# BMS028B_PinConfig.net
KiCad netlist of a schematic drawn in Altium Designer
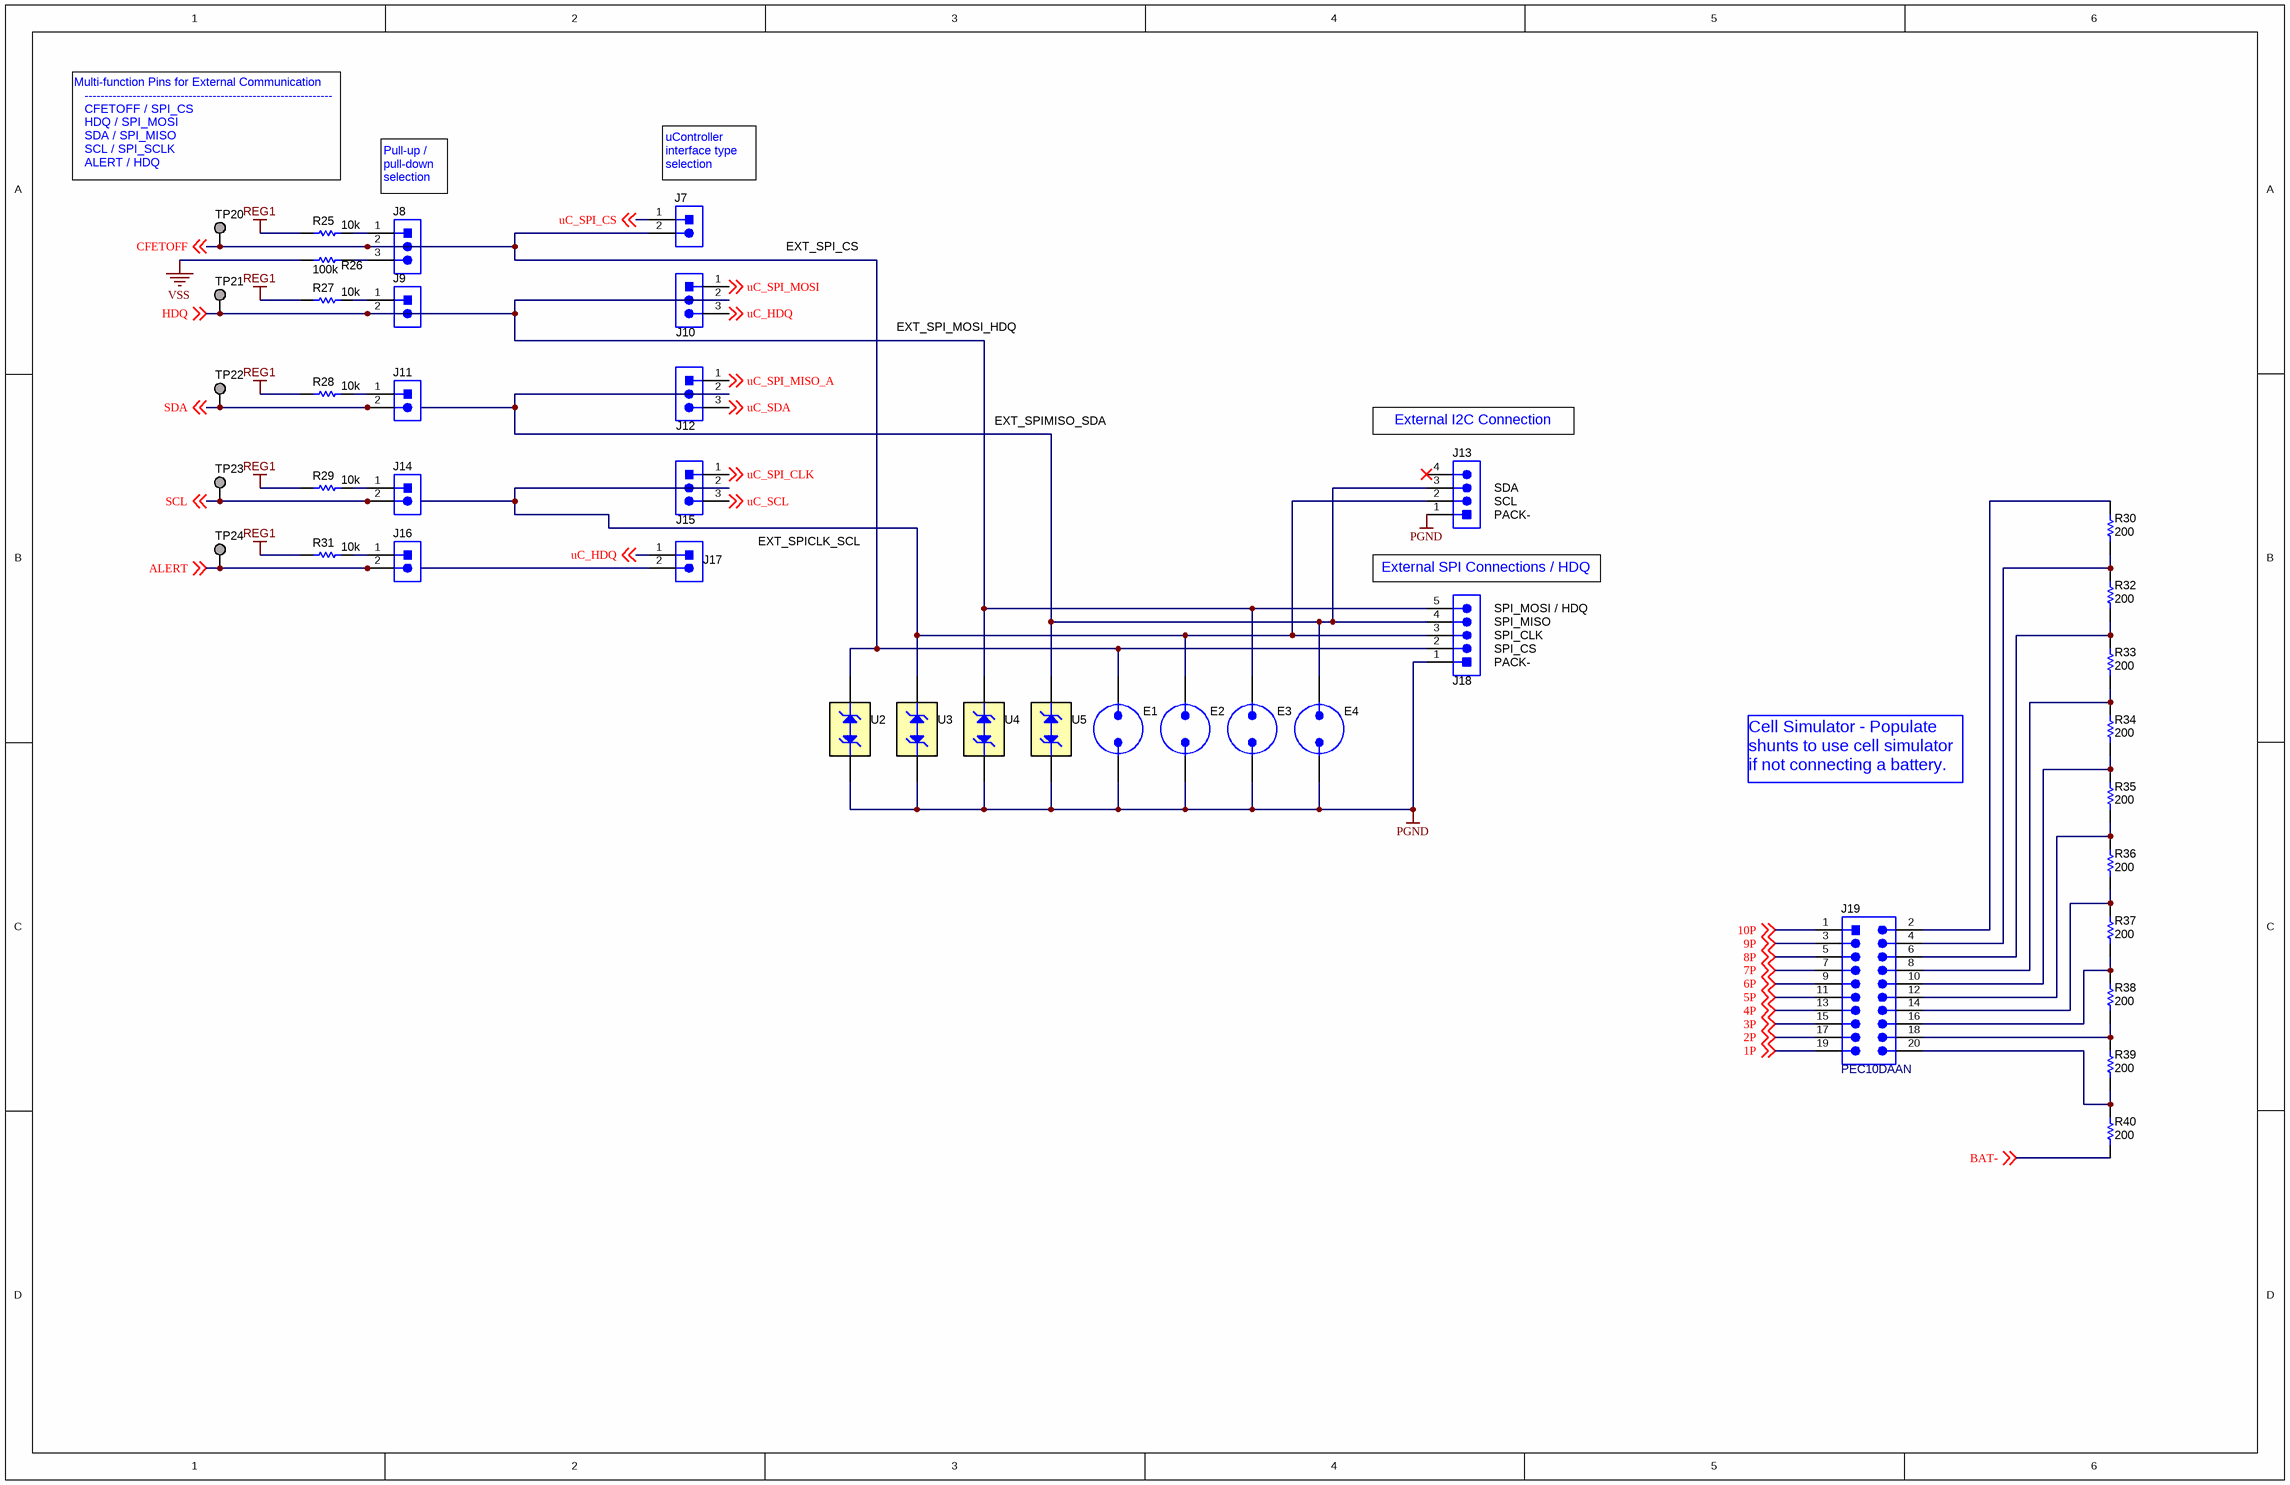
[diagram p0: BMS028B_PinConfig.SchDoc]

(export (version "E")
  (design (tool "Eeschema 10.0.6"))
  (components
    (comp (ref "E1")
      (value "Spark Gap")
      (footprint "SPARK_GAP2")
      (libsource (lib "Altium Vault - TI") (part "CMP-0079939-1"))
    )
    (comp (ref "E2")
      (value "Spark Gap")
      (footprint "SPARK_GAP2")
      (libsource (lib "Altium Vault - TI") (part "CMP-0079939-1"))
    )
    (comp (ref "E3")
      (value "Spark Gap")
      (footprint "SPARK_GAP2")
      (libsource (lib "Altium Vault - TI") (part "CMP-0079939-1"))
    )
    (comp (ref "E4")
      (value "Spark Gap")
      (footprint "SPARK_GAP2")
      (libsource (lib "Altium Vault - TI") (part "CMP-0079939-1"))
    )
    (comp (ref "J7")
      (value "PEC02SAAN")
      (footprint "CONN_PEC02SAAN")
      (description "Header, 100mil, 2x1, Tin, TH")
      (fields
        (field (name "MANUFACTURER") "Sullins Connector Solutions")
        (field (name "PUBLISHER") "Texas Instruments")
      )
      (libsource (lib "Altium Vault - TI") (part "Header_2x1"))
    )
    (comp (ref "J8")
      (value "87898-0304")
      (footprint "Molex_87898-0304")
      (description "Header, 2.54mm, 3x1, Gold, SMT")
      (fields (field (name "MANUFACTURER") "Molex") (field (name "PUBLISHER") "Texas Instruments"))
      (libsource (lib "") (part "CMP-0075388-1_1"))
    )
    (comp (ref "J9")
      (value "PEC02SAAN")
      (footprint "CONN_PEC02SAAN")
      (description "Header, 100mil, 2x1, Tin, TH")
      (fields
        (field (name "MANUFACTURER") "Sullins Connector Solutions")
        (field (name "PUBLISHER") "Texas Instruments")
      )
      (libsource (lib "Altium Vault - TI") (part "Header_2x1"))
    )
    (comp (ref "J10")
      (value "87898-0304")
      (footprint "Molex_87898-0304")
      (description "Header, 2.54mm, 3x1, Gold, SMT")
      (fields (field (name "MANUFACTURER") "Molex") (field (name "PUBLISHER") "Texas Instruments"))
      (libsource (lib "Altium Vault - TI") (part "CMP-0075388-1"))
    )
    (comp (ref "J11")
      (value "PEC02SAAN")
      (footprint "CONN_PEC02SAAN")
      (description "Header, 100mil, 2x1, Tin, TH")
      (fields
        (field (name "MANUFACTURER") "Sullins Connector Solutions")
        (field (name "PUBLISHER") "Texas Instruments")
      )
      (libsource (lib "Altium Vault - TI") (part "Header_2x1"))
    )
    (comp (ref "J12")
      (value "87898-0304")
      (footprint "Molex_87898-0304")
      (description "Header, 2.54mm, 3x1, Gold, SMT")
      (fields (field (name "MANUFACTURER") "Molex") (field (name "PUBLISHER") "Texas Instruments"))
      (libsource (lib "Altium Vault - TI") (part "CMP-0075388-1"))
    )
    (comp (ref "J13")
      (value "22/05/3041")
      (footprint "CONN_22-05-3041")
      (description "Header (friction lock), 100mil, 4x1, R/A, TH")
      (fields (field (name "MANUFACTURER") "Molex") (field (name "PUBLISHER") "Texas Instruments"))
      (libsource (lib "Altium Vault - TI") (part "CMP-0055187-1"))
    )
    (comp (ref "J14")
      (value "PEC02SAAN")
      (footprint "CONN_PEC02SAAN")
      (description "Header, 100mil, 2x1, Tin, TH")
      (fields
        (field (name "MANUFACTURER") "Sullins Connector Solutions")
        (field (name "PUBLISHER") "Texas Instruments")
      )
      (libsource (lib "Altium Vault - TI") (part "Header_2x1"))
    )
    (comp (ref "J15")
      (value "87898-0304")
      (footprint "Molex_87898-0304")
      (description "Header, 2.54mm, 3x1, Gold, SMT")
      (fields (field (name "MANUFACTURER") "Molex") (field (name "PUBLISHER") "Texas Instruments"))
      (libsource (lib "Altium Vault - TI") (part "CMP-0075388-1"))
    )
    (comp (ref "J16")
      (value "PEC02SAAN")
      (footprint "CONN_PEC02SAAN")
      (description "Header, 100mil, 2x1, Tin, TH")
      (fields
        (field (name "MANUFACTURER") "Sullins Connector Solutions")
        (field (name "PUBLISHER") "Texas Instruments")
      )
      (libsource (lib "Altium Vault - TI") (part "Header_2x1"))
    )
    (comp (ref "J17")
      (value "PEC02SAAN")
      (footprint "CONN_PEC02SAAN")
      (description "Header, 100mil, 2x1, Tin, TH")
      (fields
        (field (name "MANUFACTURER") "Sullins Connector Solutions")
        (field (name "PUBLISHER") "Texas Instruments")
      )
      (libsource (lib "Altium Vault - TI") (part "Header_2x1"))
    )
    (comp (ref "J18")
      (value "PEC05SAAN")
      (footprint "Sullins_PxC05SAAN")
      (description "Header, 2.54mm, 5x1, Tin, TH")
      (fields
        (field (name "MANUFACTURER") "Sullins Connector Solutions")
        (field (name "PUBLISHER") "Texas Instruments")
      )
      (libsource (lib "Altium Vault - TI") (part "CMP-0054597-1"))
    )
    (comp (ref "J19")
      (value "PEC10DAAN")
      (footprint "SULLINS_PEC10DAAN")
      (description "Header, 2.54mm, 10x2, Tin, TH")
      (fields (field (name "MANUFACTURER") "Sullins Connector Solutions"))
      (libsource (lib "Altium Vault - TI") (part "Header_10x2"))
    )
    (comp (ref "R25")
      (value "CRCW060310K0JNEA")
      (footprint "0603")
      (description "RES, 10 k, 5%, 0.1 W, AEC-Q200 Grade 0, 0603")
      (fields (field (name "MANUFACTURER") "Vishay-Dale") (field (name "VALUEDISPLAYED") "10k"))
      (libsource (lib "Altium Vault - TI") (part "CMP-0025701-4"))
    )
    (comp (ref "R26")
      (value "CRCW0603100KJNEA")
      (footprint "0603")
      (description "RES, 100 k, 5%, 0.1 W, AEC-Q200 Grade 0, 0603")
      (fields (field (name "MANUFACTURER") "Vishay-Dale") (field (name "VALUEDISPLAYED") "100k"))
      (libsource (lib "Altium Vault - TI") (part "Resistor"))
    )
    (comp (ref "R27")
      (value "CRCW060310K0JNEA")
      (footprint "0603")
      (description "RES, 10 k, 5%, 0.1 W, AEC-Q200 Grade 0, 0603")
      (fields (field (name "MANUFACTURER") "Vishay-Dale") (field (name "VALUEDISPLAYED") "10k"))
      (libsource (lib "Altium Vault - TI") (part "CMP-0025701-4"))
    )
    (comp (ref "R28")
      (value "CRCW060310K0JNEA")
      (footprint "0603")
      (description "RES, 10 k, 5%, 0.1 W, AEC-Q200 Grade 0, 0603")
      (fields (field (name "MANUFACTURER") "Vishay-Dale") (field (name "VALUEDISPLAYED") "10k"))
      (libsource (lib "Altium Vault - TI") (part "CMP-0025701-4"))
    )
    (comp (ref "R29")
      (value "CRCW060310K0JNEA")
      (footprint "0603")
      (description "RES, 10 k, 5%, 0.1 W, AEC-Q200 Grade 0, 0603")
      (fields (field (name "MANUFACTURER") "Vishay-Dale") (field (name "VALUEDISPLAYED") "10k"))
      (libsource (lib "Altium Vault - TI") (part "CMP-0025701-4"))
    )
    (comp (ref "R30")
      (value "CRCW1206200RFKEA")
      (footprint "1206")
      (description "RES, 200, 1%, 0.25 W, AEC-Q200 Grade 0, 1206")
      (fields (field (name "MANUFACTURER") "Vishay-Dale") (field (name "VALUEDISPLAYED") "200"))
      (libsource (lib "Altium Vault - TI") (part "Resistor"))
    )
    (comp (ref "R31")
      (value "CRCW060310K0JNEA")
      (footprint "0603")
      (description "RES, 10 k, 5%, 0.1 W, AEC-Q200 Grade 0, 0603")
      (fields (field (name "MANUFACTURER") "Vishay-Dale") (field (name "VALUEDISPLAYED") "10k"))
      (libsource (lib "Altium Vault - TI") (part "CMP-0025701-4"))
    )
    (comp (ref "R32")
      (value "CRCW1206200RFKEA")
      (footprint "1206")
      (description "RES, 200, 1%, 0.25 W, AEC-Q200 Grade 0, 1206")
      (fields (field (name "MANUFACTURER") "Vishay-Dale") (field (name "VALUEDISPLAYED") "200"))
      (libsource (lib "Altium Vault - TI") (part "Resistor"))
    )
    (comp (ref "R33")
      (value "CRCW1206200RFKEA")
      (footprint "1206")
      (description "RES, 200, 1%, 0.25 W, AEC-Q200 Grade 0, 1206")
      (fields (field (name "MANUFACTURER") "Vishay-Dale") (field (name "VALUEDISPLAYED") "200"))
      (libsource (lib "Altium Vault - TI") (part "Resistor"))
    )
    (comp (ref "R34")
      (value "CRCW1206200RFKEA")
      (footprint "1206")
      (description "RES, 200, 1%, 0.25 W, AEC-Q200 Grade 0, 1206")
      (fields (field (name "MANUFACTURER") "Vishay-Dale") (field (name "VALUEDISPLAYED") "200"))
      (libsource (lib "Altium Vault - TI") (part "Resistor"))
    )
    (comp (ref "R35")
      (value "CRCW1206200RFKEA")
      (footprint "1206")
      (description "RES, 200, 1%, 0.25 W, AEC-Q200 Grade 0, 1206")
      (fields (field (name "MANUFACTURER") "Vishay-Dale") (field (name "VALUEDISPLAYED") "200"))
      (libsource (lib "Altium Vault - TI") (part "Resistor"))
    )
    (comp (ref "R36")
      (value "CRCW1206200RFKEA")
      (footprint "1206")
      (description "RES, 200, 1%, 0.25 W, AEC-Q200 Grade 0, 1206")
      (fields (field (name "MANUFACTURER") "Vishay-Dale") (field (name "VALUEDISPLAYED") "200"))
      (libsource (lib "Altium Vault - TI") (part "Resistor"))
    )
    (comp (ref "R37")
      (value "CRCW1206200RFKEA")
      (footprint "1206")
      (description "RES, 200, 1%, 0.25 W, AEC-Q200 Grade 0, 1206")
      (fields (field (name "MANUFACTURER") "Vishay-Dale") (field (name "VALUEDISPLAYED") "200"))
      (libsource (lib "Altium Vault - TI") (part "Resistor"))
    )
    (comp (ref "R38")
      (value "CRCW1206200RFKEA")
      (footprint "1206")
      (description "RES, 200, 1%, 0.25 W, AEC-Q200 Grade 0, 1206")
      (fields (field (name "MANUFACTURER") "Vishay-Dale") (field (name "VALUEDISPLAYED") "200"))
      (libsource (lib "Altium Vault - TI") (part "Resistor"))
    )
    (comp (ref "R39")
      (value "CRCW1206200RFKEA")
      (footprint "1206")
      (description "RES, 200, 1%, 0.25 W, AEC-Q200 Grade 0, 1206")
      (fields (field (name "MANUFACTURER") "Vishay-Dale") (field (name "VALUEDISPLAYED") "200"))
      (libsource (lib "Altium Vault - TI") (part "Resistor"))
    )
    (comp (ref "R40")
      (value "CRCW1206200RFKEA")
      (footprint "1206")
      (description "RES, 200, 1%, 0.25 W, AEC-Q200 Grade 0, 1206")
      (fields (field (name "MANUFACTURER") "Vishay-Dale") (field (name "VALUEDISPLAYED") "200"))
      (libsource (lib "Altium Vault - TI") (part "Resistor"))
    )
    (comp (ref "TP20")
      (value "TESTPOINT")
      (footprint "TP_50MIL-25MILHOLE")
      (description "TEST POINT.  No entry in BOM.")
      (libsource (lib "Altium Vault - TI") (part "TESTPOINT"))
    )
    (comp (ref "TP21")
      (value "TESTPOINT")
      (footprint "TP_50MIL-25MILHOLE")
      (description "TEST POINT.  No entry in BOM.")
      (libsource (lib "Altium Vault - TI") (part "TESTPOINT"))
    )
    (comp (ref "TP22")
      (value "TESTPOINT")
      (footprint "TP_50MIL-25MILHOLE")
      (description "TEST POINT.  No entry in BOM.")
      (libsource (lib "Altium Vault - TI") (part "TESTPOINT"))
    )
    (comp (ref "TP23")
      (value "TESTPOINT")
      (footprint "TP_50MIL-25MILHOLE")
      (description "TEST POINT.  No entry in BOM.")
      (libsource (lib "Altium Vault - TI") (part "TESTPOINT"))
    )
    (comp (ref "TP24")
      (value "TESTPOINT")
      (footprint "TP_50MIL-25MILHOLE")
      (description "TEST POINT.  No entry in BOM.")
      (libsource (lib "Altium Vault - TI") (part "TESTPOINT"))
    )
    (comp (ref "U2")
      (value "TPD1E10B06DPYR")
      (footprint "DPY0002A")
      (description "Single-Channel ESD in 0402 Package With 10pF Capacitance and 6V Breakdown, DPY0002A (X1SON-2)")
      (fields
        (field (name "MANUFACTURER") "Texas Instruments")
        (field (name "ALTERNATE PARTNUMBER") "TPD1E10B06DPYT")
      )
      (libsource (lib "Altium Vault - TI") (part "TPD1E10B06"))
    )
    (comp (ref "U3")
      (value "TPD1E10B06DPYR")
      (footprint "DPY0002A")
      (description "Single-Channel ESD in 0402 Package With 10pF Capacitance and 6V Breakdown, DPY0002A (X1SON-2)")
      (fields
        (field (name "MANUFACTURER") "Texas Instruments")
        (field (name "ALTERNATE PARTNUMBER") "TPD1E10B06DPYT")
      )
      (libsource (lib "Altium Vault - TI") (part "TPD1E10B06"))
    )
    (comp (ref "U4")
      (value "TPD1E10B06DPYR")
      (footprint "DPY0002A")
      (description "Single-Channel ESD in 0402 Package With 10pF Capacitance and 6V Breakdown, DPY0002A (X1SON-2)")
      (fields
        (field (name "MANUFACTURER") "Texas Instruments")
        (field (name "ALTERNATE PARTNUMBER") "TPD1E10B06DPYT")
      )
      (libsource (lib "Altium Vault - TI") (part "TPD1E10B06"))
    )
    (comp (ref "U5")
      (value "TPD1E10B06DPYR")
      (footprint "DPY0002A")
      (description "Single-Channel ESD in 0402 Package With 10pF Capacitance and 6V Breakdown, DPY0002A (X1SON-2)")
      (fields
        (field (name "MANUFACTURER") "Texas Instruments")
        (field (name "ALTERNATE PARTNUMBER") "TPD1E10B06DPYT")
      )
      (libsource (lib "Altium Vault - TI") (part "TPD1E10B06"))
    )
  )
  (nets
    (net (code "1") (name "1P") (class "Default")
      (node (ref "J19") (pin "19") (pinfunction "19_19") (pintype "passive"))
    )
    (net (code "2") (name "2P") (class "Default")
      (node (ref "J19") (pin "17") (pinfunction "17_17") (pintype "passive"))
    )
    (net (code "3") (name "3P") (class "Default")
      (node (ref "J19") (pin "15") (pinfunction "15_15") (pintype "passive"))
    )
    (net (code "4") (name "4P") (class "Default")
      (node (ref "J19") (pin "13") (pinfunction "13_13") (pintype "passive"))
    )
    (net (code "5") (name "5P") (class "Default")
      (node (ref "J19") (pin "11") (pinfunction "11_11") (pintype "passive"))
    )
    (net (code "6") (name "6P") (class "Default")
      (node (ref "J19") (pin "9") (pinfunction "9_9") (pintype "passive"))
    )
    (net (code "7") (name "7P") (class "Default")
      (node (ref "J19") (pin "7") (pinfunction "7_7") (pintype "passive"))
    )
    (net (code "8") (name "8P") (class "Default")
      (node (ref "J19") (pin "5") (pinfunction "5_5") (pintype "passive"))
    )
    (net (code "9") (name "9P") (class "Default")
      (node (ref "J19") (pin "3") (pinfunction "3_3") (pintype "passive"))
    )
    (net (code "10") (name "10P") (class "Default")
      (node (ref "J19") (pin "1") (pinfunction "1_1") (pintype "passive"))
    )
    (net (code "11") (name "ALERT") (class "Default")
      (node (ref "J16") (pin "2") (pinfunction "2_2") (pintype "passive"))
      (node (ref "J17") (pin "2") (pinfunction "2_2") (pintype "passive"))
      (node (ref "TP24") (pin "1") (pintype "passive"))
    )
    (net (code "12") (name "BAT-") (class "Default")
      (node (ref "R40") (pin "1") (pinfunction "1_1") (pintype "passive"))
    )
    (net (code "13") (name "CFETOFF") (class "Default")
      (node (ref "E1") (pin "1") (pinfunction "1_1") (pintype "passive"))
      (node (ref "J18") (pin "2") (pinfunction "2_2") (pintype "passive"))
      (node (ref "J7") (pin "2") (pinfunction "2_2") (pintype "passive"))
      (node (ref "J8") (pin "2") (pinfunction "2_2") (pintype "passive"))
      (node (ref "TP20") (pin "1") (pintype "passive"))
      (node (ref "U2") (pin "1") (pinfunction "K_1") (pintype "passive"))
    )
    (net (code "14") (name "HDQ") (class "Default")
      (node (ref "E3") (pin "1") (pinfunction "1_1") (pintype "passive"))
      (node (ref "J10") (pin "2") (pinfunction "2_2") (pintype "passive"))
      (node (ref "J18") (pin "5") (pinfunction "5_5") (pintype "passive"))
      (node (ref "J9") (pin "2") (pinfunction "2_2") (pintype "passive"))
      (node (ref "TP21") (pin "1") (pintype "passive"))
      (node (ref "U4") (pin "1") (pinfunction "K_1") (pintype "passive"))
    )
    (net (code "15") (name "Net-(J8-Pad1)") (class "Default")
      (node (ref "J8") (pin "1") (pinfunction "1_1") (pintype "passive"))
      (node (ref "R25") (pin "2") (pinfunction "2_2") (pintype "passive"))
    )
    (net (code "16") (name "Net-(J8-Pad3)") (class "Default")
      (node (ref "J8") (pin "3") (pinfunction "3_3") (pintype "passive"))
      (node (ref "R26") (pin "2") (pinfunction "2_2") (pintype "passive"))
    )
    (net (code "17") (name "Net-(J9-Pad1)") (class "Default")
      (node (ref "J9") (pin "1") (pinfunction "1_1") (pintype "passive"))
      (node (ref "R27") (pin "2") (pinfunction "2_2") (pintype "passive"))
    )
    (net (code "18") (name "Net-(J11-Pad1)") (class "Default")
      (node (ref "J11") (pin "1") (pinfunction "1_1") (pintype "passive"))
      (node (ref "R28") (pin "2") (pinfunction "2_2") (pintype "passive"))
    )
    (net (code "19") (name "Net-(J14-Pad1)") (class "Default")
      (node (ref "J14") (pin "1") (pinfunction "1_1") (pintype "passive"))
      (node (ref "R29") (pin "2") (pinfunction "2_2") (pintype "passive"))
    )
    (net (code "20") (name "Net-(J16-Pad1)") (class "Default")
      (node (ref "J16") (pin "1") (pinfunction "1_1") (pintype "passive"))
      (node (ref "R31") (pin "2") (pinfunction "2_2") (pintype "passive"))
    )
    (net (code "21") (name "Net-(J19-Pad2)") (class "Default")
      (node (ref "J19") (pin "2") (pinfunction "2_2") (pintype "passive"))
      (node (ref "R30") (pin "2") (pinfunction "2_2") (pintype "passive"))
    )
    (net (code "22") (name "Net-(J19-Pad4)") (class "Default")
      (node (ref "J19") (pin "4") (pinfunction "4_4") (pintype "passive"))
      (node (ref "R30") (pin "1") (pinfunction "1_1") (pintype "passive"))
      (node (ref "R32") (pin "2") (pinfunction "2_2") (pintype "passive"))
    )
    (net (code "23") (name "Net-(J19-Pad6)") (class "Default")
      (node (ref "J19") (pin "6") (pinfunction "6_6") (pintype "passive"))
      (node (ref "R32") (pin "1") (pinfunction "1_1") (pintype "passive"))
      (node (ref "R33") (pin "2") (pinfunction "2_2") (pintype "passive"))
    )
    (net (code "24") (name "Net-(J19-Pad8)") (class "Default")
      (node (ref "J19") (pin "8") (pinfunction "8_8") (pintype "passive"))
      (node (ref "R33") (pin "1") (pinfunction "1_1") (pintype "passive"))
      (node (ref "R34") (pin "2") (pinfunction "2_2") (pintype "passive"))
    )
    (net (code "25") (name "Net-(J19-Pad10)") (class "Default")
      (node (ref "J19") (pin "10") (pinfunction "10_10") (pintype "passive"))
      (node (ref "R34") (pin "1") (pinfunction "1_1") (pintype "passive"))
      (node (ref "R35") (pin "2") (pinfunction "2_2") (pintype "passive"))
    )
    (net (code "26") (name "Net-(J19-Pad12)") (class "Default")
      (node (ref "J19") (pin "12") (pinfunction "12_12") (pintype "passive"))
      (node (ref "R35") (pin "1") (pinfunction "1_1") (pintype "passive"))
      (node (ref "R36") (pin "2") (pinfunction "2_2") (pintype "passive"))
    )
    (net (code "27") (name "Net-(J19-Pad14)") (class "Default")
      (node (ref "J19") (pin "14") (pinfunction "14_14") (pintype "passive"))
      (node (ref "R36") (pin "1") (pinfunction "1_1") (pintype "passive"))
      (node (ref "R37") (pin "2") (pinfunction "2_2") (pintype "passive"))
    )
    (net (code "28") (name "Net-(J19-Pad16)") (class "Default")
      (node (ref "J19") (pin "16") (pinfunction "16_16") (pintype "passive"))
      (node (ref "R37") (pin "1") (pinfunction "1_1") (pintype "passive"))
      (node (ref "R38") (pin "2") (pinfunction "2_2") (pintype "passive"))
    )
    (net (code "29") (name "Net-(J19-Pad18)") (class "Default")
      (node (ref "J19") (pin "18") (pinfunction "18_18") (pintype "passive"))
      (node (ref "R38") (pin "1") (pinfunction "1_1") (pintype "passive"))
      (node (ref "R39") (pin "2") (pinfunction "2_2") (pintype "passive"))
    )
    (net (code "30") (name "Net-(J19-Pad20)") (class "Default")
      (node (ref "J19") (pin "20") (pinfunction "20_20") (pintype "passive"))
      (node (ref "R39") (pin "1") (pinfunction "1_1") (pintype "passive"))
      (node (ref "R40") (pin "2") (pinfunction "2_2") (pintype "passive"))
    )
    (net (code "31") (name "PGND") (class "Default")
      (node (ref "E1") (pin "2") (pinfunction "2_2") (pintype "passive"))
      (node (ref "E2") (pin "2") (pinfunction "2_2") (pintype "passive"))
      (node (ref "E3") (pin "2") (pinfunction "2_2") (pintype "passive"))
      (node (ref "E4") (pin "2") (pinfunction "2_2") (pintype "passive"))
      (node (ref "J13") (pin "1") (pinfunction "1_1") (pintype "passive"))
      (node (ref "J18") (pin "1") (pinfunction "1_1") (pintype "passive"))
      (node (ref "U2") (pin "2") (pinfunction "A_2") (pintype "passive"))
      (node (ref "U3") (pin "2") (pinfunction "A_2") (pintype "passive"))
      (node (ref "U4") (pin "2") (pinfunction "A_2") (pintype "passive"))
      (node (ref "U5") (pin "2") (pinfunction "A_2") (pintype "passive"))
    )
    (net (code "32") (name "REG1") (class "Default")
      (node (ref "R25") (pin "1") (pinfunction "1_1") (pintype "passive"))
      (node (ref "R27") (pin "1") (pinfunction "1_1") (pintype "passive"))
      (node (ref "R28") (pin "1") (pinfunction "1_1") (pintype "passive"))
      (node (ref "R29") (pin "1") (pinfunction "1_1") (pintype "passive"))
      (node (ref "R31") (pin "1") (pinfunction "1_1") (pintype "passive"))
    )
    (net (code "33") (name "SCL") (class "Default")
      (node (ref "E2") (pin "1") (pinfunction "1_1") (pintype "passive"))
      (node (ref "J13") (pin "2") (pinfunction "2_2") (pintype "passive"))
      (node (ref "J14") (pin "2") (pinfunction "2_2") (pintype "passive"))
      (node (ref "J15") (pin "2") (pinfunction "2_2") (pintype "passive"))
      (node (ref "J18") (pin "3") (pinfunction "3_3") (pintype "passive"))
      (node (ref "TP23") (pin "1") (pintype "passive"))
      (node (ref "U3") (pin "1") (pinfunction "K_1") (pintype "passive"))
    )
    (net (code "34") (name "SDA") (class "Default")
      (node (ref "E4") (pin "1") (pinfunction "1_1") (pintype "passive"))
      (node (ref "J11") (pin "2") (pinfunction "2_2") (pintype "passive"))
      (node (ref "J12") (pin "2") (pinfunction "2_2") (pintype "passive"))
      (node (ref "J13") (pin "3") (pinfunction "3_3") (pintype "passive"))
      (node (ref "J18") (pin "4") (pinfunction "4_4") (pintype "passive"))
      (node (ref "TP22") (pin "1") (pintype "passive"))
      (node (ref "U5") (pin "1") (pinfunction "K_1") (pintype "passive"))
    )
    (net (code "35") (name "VSS") (class "Default")
      (node (ref "R26") (pin "1") (pinfunction "1_1") (pintype "passive"))
    )
    (net (code "36") (name "uC_HDQ") (class "Default")
      (node (ref "J10") (pin "3") (pinfunction "3_3") (pintype "passive"))
      (node (ref "J17") (pin "1") (pinfunction "1_1") (pintype "passive"))
    )
    (net (code "37") (name "uC_SCL") (class "Default")
      (node (ref "J15") (pin "3") (pinfunction "3_3") (pintype "passive"))
    )
    (net (code "38") (name "uC_SDA") (class "Default")
      (node (ref "J12") (pin "3") (pinfunction "3_3") (pintype "passive"))
    )
    (net (code "39") (name "uC_SPI_CLK") (class "Default")
      (node (ref "J15") (pin "1") (pinfunction "1_1") (pintype "passive"))
    )
    (net (code "40") (name "uC_SPI_CS") (class "Default")
      (node (ref "J7") (pin "1") (pinfunction "1_1") (pintype "passive"))
    )
    (net (code "41") (name "uC_SPI_MISO_A") (class "Default")
      (node (ref "J12") (pin "1") (pinfunction "1_1") (pintype "passive"))
    )
    (net (code "42") (name "uC_SPI_MOSI") (class "Default")
      (node (ref "J10") (pin "1") (pinfunction "1_1") (pintype "passive"))
    )
    (net (code "43") (name "unconnected-(J13-Pad4)") (class "Default")
      (node (ref "J13") (pin "4") (pinfunction "4_4") (pintype "passive+no_connect"))
    )
  )
)
